# Trackpoint_Amplifier.net
KiCad netlist of a schematic drawn in Altium Designer
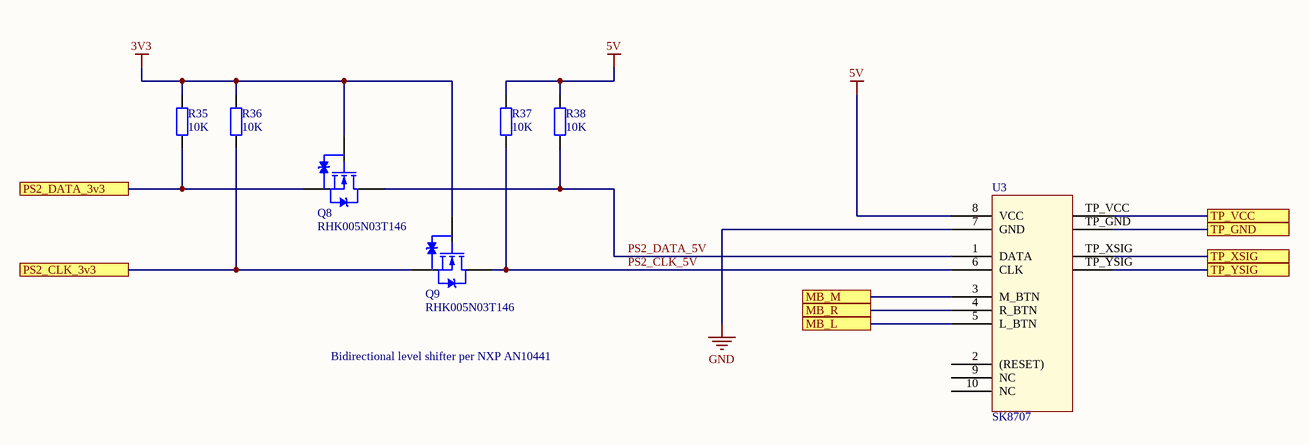
[diagram p0: Trackpoint Amplifier.SchDoc]

(export (version "E")
  (design (tool "Eeschema 10.0.6"))
  (components
    (comp (ref "Q8")
      (value "RHK005N03T146")
      (footprint "RHK005N03T146 - SOT95P280X110-3N")
      (description "MOSFET N-CH 30V 500MA")
      (libsource (lib "KBuchka-IntLib") (part "RHK005N03T146"))
    )
    (comp (ref "Q9")
      (value "RHK005N03T146")
      (footprint "RHK005N03T146 - SOT95P280X110-3N")
      (description "MOSFET N-CH 30V 500MA")
      (libsource (lib "KBuchka-IntLib") (part "RHK005N03T146"))
    )
    (comp (ref "R35")
      (value "10K")
      (footprint "RES_SM0603_YAGEORC_N")
      (description "RES 10K SM0603 YAGEO RC_L")
      (fields
        (field (name "MANUFACTURER") "Yageo")
        (field (name "MANUFACTURER PART NUMBER") "RC0603FR-0710KL")
      )
      (libsource (lib "Yageo") (part "RC0603FR-0710KL"))
    )
    (comp (ref "R36")
      (value "10K")
      (footprint "RES_SM0603_YAGEORC_N")
      (description "RES 10K SM0603 YAGEO RC_L")
      (fields
        (field (name "MANUFACTURER") "Yageo")
        (field (name "MANUFACTURER PART NUMBER") "RC0603FR-0710KL")
      )
      (libsource (lib "Yageo") (part "RC0603FR-0710KL"))
    )
    (comp (ref "R37")
      (value "10K")
      (footprint "RES_SM0603_YAGEORC_N")
      (description "RES 10K SM0603 YAGEO RC_L")
      (fields
        (field (name "MANUFACTURER") "Yageo")
        (field (name "MANUFACTURER PART NUMBER") "RC0603FR-0710KL")
      )
      (libsource (lib "Yageo") (part "RC0603FR-0710KL"))
    )
    (comp (ref "R38")
      (value "10K")
      (footprint "RES_SM0603_YAGEORC_N")
      (description "RES 10K SM0603 YAGEO RC_L")
      (fields
        (field (name "MANUFACTURER") "Yageo")
        (field (name "MANUFACTURER PART NUMBER") "RC0603FR-0710KL")
      )
      (libsource (lib "Yageo") (part "RC0603FR-0710KL"))
    )
    (comp (ref "U3") (value "SK8707") (footprint "SK8707") (libsource (lib "KBuchka-IntLib") (part "SK8707")))
  )
  (nets
    (net (code "1") (name "/MB_L") (class "Default")
      (node (ref "U3") (pin "5") (pinfunction "L_BTN_5") (pintype "passive"))
    )
    (net (code "2") (name "/MB_M") (class "Default")
      (node (ref "U3") (pin "3") (pinfunction "M_BTN_3") (pintype "passive"))
    )
    (net (code "3") (name "/MB_R") (class "Default")
      (node (ref "U3") (pin "4") (pinfunction "R_BTN_4") (pintype "passive"))
    )
    (net (code "4") (name "/PS2_CLK_3v3") (class "Default")
      (node (ref "Q9") (pin "1") (pinfunction "S_1") (pintype "passive"))
      (node (ref "R36") (pin "1") (pintype "passive"))
    )
    (net (code "5") (name "/PS2_CLK_5V") (class "Default")
      (node (ref "Q9") (pin "3") (pinfunction "D_3") (pintype "passive"))
      (node (ref "R37") (pin "1") (pintype "passive"))
      (node (ref "U3") (pin "6") (pinfunction "CLK_6") (pintype "passive"))
    )
    (net (code "6") (name "/PS2_DATA_3v3") (class "Default")
      (node (ref "Q8") (pin "1") (pinfunction "S_1") (pintype "passive"))
      (node (ref "R35") (pin "1") (pintype "passive"))
    )
    (net (code "7") (name "/PS2_DATA_5V") (class "Default")
      (node (ref "Q8") (pin "3") (pinfunction "D_3") (pintype "passive"))
      (node (ref "R38") (pin "1") (pintype "passive"))
      (node (ref "U3") (pin "1") (pinfunction "DATA_1") (pintype "passive"))
    )
    (net (code "8") (name "/TP_GND") (class "Default")
      (node (ref "U3") (pin "TP_GND") (pinfunction "12_TP_GND") (pintype "passive"))
    )
    (net (code "9") (name "/TP_VCC") (class "Default")
      (node (ref "U3") (pin "TP_VCC") (pinfunction "11_TP_VCC") (pintype "passive"))
    )
    (net (code "10") (name "/TP_XSIG") (class "Default")
      (node (ref "U3") (pin "TP_XSIG") (pinfunction "14_TP_XSIG") (pintype "passive"))
    )
    (net (code "11") (name "/TP_YSIG") (class "Default")
      (node (ref "U3") (pin "TP_YSIG") (pinfunction "13_TP_YSIG") (pintype "passive"))
    )
    (net (code "12") (name "3V3") (class "Default")
      (node (ref "Q8") (pin "2") (pinfunction "G_2") (pintype "passive"))
      (node (ref "Q9") (pin "2") (pinfunction "G_2") (pintype "passive"))
      (node (ref "R35") (pin "2") (pintype "passive"))
      (node (ref "R36") (pin "2") (pintype "passive"))
    )
    (net (code "13") (name "5V") (class "Default")
      (node (ref "R37") (pin "2") (pintype "passive"))
      (node (ref "R38") (pin "2") (pintype "passive"))
      (node (ref "U3") (pin "8") (pinfunction "VCC_8") (pintype "passive"))
    )
    (net (code "14") (name "GND") (class "Default")
      (node (ref "U3") (pin "7") (pinfunction "GND_7") (pintype "passive"))
    )
    (net (code "15") (name "unconnected-(U3-(RESET)-Pad2)") (class "Default")
      (node (ref "U3") (pin "2") (pinfunction "(RESET)_2") (pintype "passive"))
    )
    (net (code "16") (name "unconnected-(U3-NC-Pad9)") (class "Default")
      (node (ref "U3") (pin "9") (pinfunction "NC_9") (pintype "passive"))
    )
    (net (code "17") (name "unconnected-(U3-NC-Pad10)") (class "Default")
      (node (ref "U3") (pin "10") (pinfunction "NC_10") (pintype "passive"))
    )
  )
)
